# mLamp.net
KiCad netlist of a schematic drawn in EAGLE
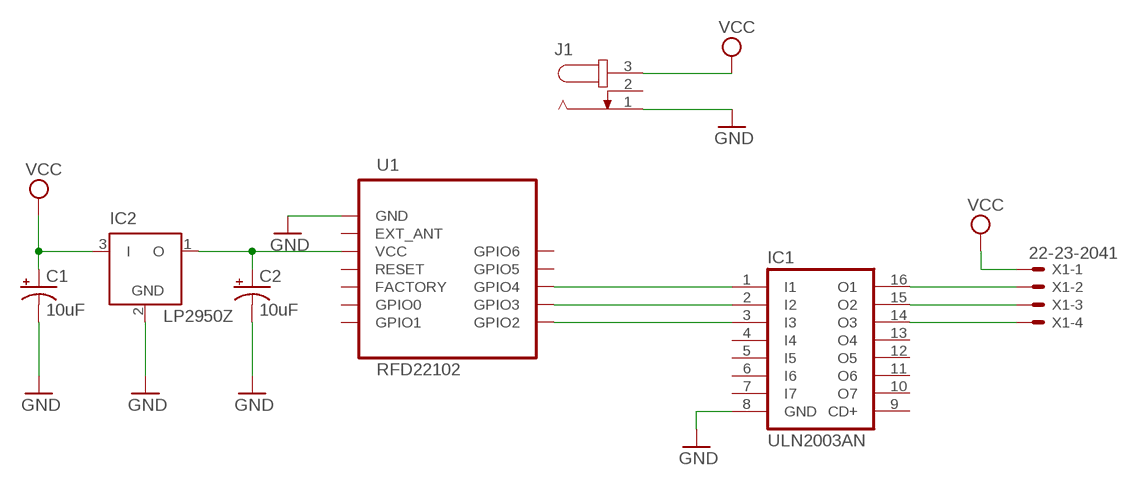
[diagram p0: schematic, sheet 1]

(export (version "E")
  (design (tool "Eeschema 10.0.6"))
  (components
    (comp (ref "C1")
      (value "10uF")
      (footprint "eagle-import:CPOL-RADIAL-10UF-25V")
      (libsource (lib "eagle-import") (part "CAP_POLPTH2"))
    )
    (comp (ref "C2")
      (value "10uF")
      (footprint "eagle-import:CPOL-RADIAL-10UF-25V")
      (libsource (lib "eagle-import") (part "CAP_POLPTH2"))
    )
    (comp (ref "IC1")
      (value "ULN2003AN")
      (footprint "eagle-import:DIL16")
      (libsource (lib "eagle-import") (part "ULN2003AN"))
    )
    (comp (ref "IC2")
      (value "LP2950Z")
      (footprint "eagle-import:TO92")
      (libsource (lib "eagle-import") (part "LP2950Z"))
    )
    (comp (ref "J1")
      (value "JACK-PLUG0")
      (footprint "eagle-import:SPC4077")
      (libsource (lib "eagle-import") (part "JACK-PLUG0"))
    )
    (comp (ref "U1")
      (value "RFD22102")
      (footprint "eagle-import:RFD22102")
      (libsource (lib "eagle-import") (part "RFD22102"))
    )
    (comp (ref "X1")
      (value "22-23-2041")
      (footprint "eagle-import:22-23-2041")
      (fields (field (name "MF") "MOLEX"))
      (libsource (lib "eagle-import") (part "22-23-2041"))
    )
  )
  (nets
    (net (code "1") (name "GND") (class "Default")
      (node (ref "C1") (pin "2") (pinfunction "-_2") (pintype "passive"))
      (node (ref "C2") (pin "2") (pinfunction "-_2") (pintype "passive"))
      (node (ref "IC1") (pin "8") (pinfunction "GND_8") (pintype "power_in"))
      (node (ref "IC2") (pin "2") (pinfunction "GND_2") (pintype "power_in"))
      (node (ref "J1") (pin "1") (pinfunction "1_1") (pintype "passive"))
      (node (ref "U1") (pin "GND") (pinfunction "GND_GND") (pintype "power_in"))
    )
    (net (code "2") (name "Net-(C2-+)") (class "Default")
      (node (ref "C2") (pin "1") (pinfunction "+_1") (pintype "passive"))
      (node (ref "IC2") (pin "1") (pinfunction "O_1") (pintype "input"))
      (node (ref "U1") (pin "VCC") (pinfunction "VCC_VCC") (pintype "power_in"))
    )
    (net (code "3") (name "Net-(IC1-I1)") (class "Default")
      (node (ref "IC1") (pin "1") (pinfunction "I1_1") (pintype "input"))
      (node (ref "U1") (pin "GPIO4") (pinfunction "GPIO4_GPIO4") (pintype "bidirectional"))
    )
    (net (code "4") (name "Net-(IC1-I2)") (class "Default")
      (node (ref "IC1") (pin "2") (pinfunction "I2_2") (pintype "input"))
      (node (ref "U1") (pin "GPIO3") (pinfunction "GPIO3_GPIO3") (pintype "bidirectional"))
    )
    (net (code "5") (name "Net-(IC1-I3)") (class "Default")
      (node (ref "IC1") (pin "3") (pinfunction "I3_3") (pintype "input"))
      (node (ref "U1") (pin "GPIO2") (pinfunction "GPIO2_GPIO2") (pintype "bidirectional"))
    )
    (net (code "6") (name "Net-(IC1-O1)") (class "Default")
      (node (ref "IC1") (pin "16") (pinfunction "O1_16") (pintype "open_collector"))
      (node (ref "X1") (pin "2") (pinfunction "S_2") (pintype "passive"))
    )
    (net (code "7") (name "Net-(IC1-O2)") (class "Default")
      (node (ref "IC1") (pin "15") (pinfunction "O2_15") (pintype "open_collector"))
      (node (ref "X1") (pin "3") (pinfunction "S_3") (pintype "passive"))
    )
    (net (code "8") (name "Net-(IC1-O3)") (class "Default")
      (node (ref "IC1") (pin "14") (pinfunction "O3_14") (pintype "open_collector"))
      (node (ref "X1") (pin "4") (pinfunction "S_4") (pintype "passive"))
    )
    (net (code "9") (name "VCC") (class "Default")
      (node (ref "C1") (pin "1") (pinfunction "+_1") (pintype "passive"))
      (node (ref "IC2") (pin "3") (pinfunction "I_3") (pintype "input"))
      (node (ref "J1") (pin "3") (pinfunction "3_3") (pintype "passive"))
      (node (ref "X1") (pin "1") (pinfunction "S_1") (pintype "passive"))
    )
    (net (code "10") (name "unconnected-(IC1-CD+-Pad9)") (class "Default")
      (node (ref "IC1") (pin "9") (pinfunction "CD+_9") (pintype "passive"))
    )
    (net (code "11") (name "unconnected-(IC1-I4-Pad4)") (class "Default")
      (node (ref "IC1") (pin "4") (pinfunction "I4_4") (pintype "input"))
    )
    (net (code "12") (name "unconnected-(IC1-I5-Pad5)") (class "Default")
      (node (ref "IC1") (pin "5") (pinfunction "I5_5") (pintype "input"))
    )
    (net (code "13") (name "unconnected-(IC1-I6-Pad6)") (class "Default")
      (node (ref "IC1") (pin "6") (pinfunction "I6_6") (pintype "input"))
    )
    (net (code "14") (name "unconnected-(IC1-I7-Pad7)") (class "Default")
      (node (ref "IC1") (pin "7") (pinfunction "I7_7") (pintype "input"))
    )
    (net (code "15") (name "unconnected-(IC1-O4-Pad13)") (class "Default")
      (node (ref "IC1") (pin "13") (pinfunction "O4_13") (pintype "open_collector"))
    )
    (net (code "16") (name "unconnected-(IC1-O5-Pad12)") (class "Default")
      (node (ref "IC1") (pin "12") (pinfunction "O5_12") (pintype "open_collector"))
    )
    (net (code "17") (name "unconnected-(IC1-O6-Pad11)") (class "Default")
      (node (ref "IC1") (pin "11") (pinfunction "O6_11") (pintype "open_collector"))
    )
    (net (code "18") (name "unconnected-(IC1-O7-Pad10)") (class "Default")
      (node (ref "IC1") (pin "10") (pinfunction "O7_10") (pintype "open_collector"))
    )
    (net (code "19") (name "unconnected-(J1-Pad2)") (class "Default")
      (node (ref "J1") (pin "2") (pinfunction "2_2") (pintype "passive"))
    )
    (net (code "20") (name "unconnected-(U1-PadEXT_ANT)") (class "Default")
      (node (ref "U1") (pin "EXT_ANT") (pinfunction "EXT_ANT_EXT_ANT") (pintype "no_connect"))
    )
    (net (code "21") (name "unconnected-(U1-PadFACTORY)") (class "Default")
      (node (ref "U1") (pin "FACTORY") (pinfunction "FACTORY_FACTORY") (pintype "bidirectional"))
    )
    (net (code "22") (name "unconnected-(U1-PadGPIO0)") (class "Default")
      (node (ref "U1") (pin "GPIO0") (pinfunction "GPIO0_GPIO0") (pintype "bidirectional"))
    )
    (net (code "23") (name "unconnected-(U1-PadGPIO1)") (class "Default")
      (node (ref "U1") (pin "GPIO1") (pinfunction "GPIO1_GPIO1") (pintype "bidirectional"))
    )
    (net (code "24") (name "unconnected-(U1-PadGPIO5)") (class "Default")
      (node (ref "U1") (pin "GPIO5") (pinfunction "GPIO5_GPIO5") (pintype "bidirectional"))
    )
    (net (code "25") (name "unconnected-(U1-PadGPIO6)") (class "Default")
      (node (ref "U1") (pin "GPIO6") (pinfunction "GPIO6_GPIO6") (pintype "bidirectional"))
    )
    (net (code "26") (name "unconnected-(U1-PadRESET)") (class "Default")
      (node (ref "U1") (pin "RESET") (pinfunction "RESET_RESET") (pintype "bidirectional"))
    )
  )
)
